# SCH_transistor-as-switch_2025-12-18.net
KiCad netlist of a schematic drawn in EasyEDA
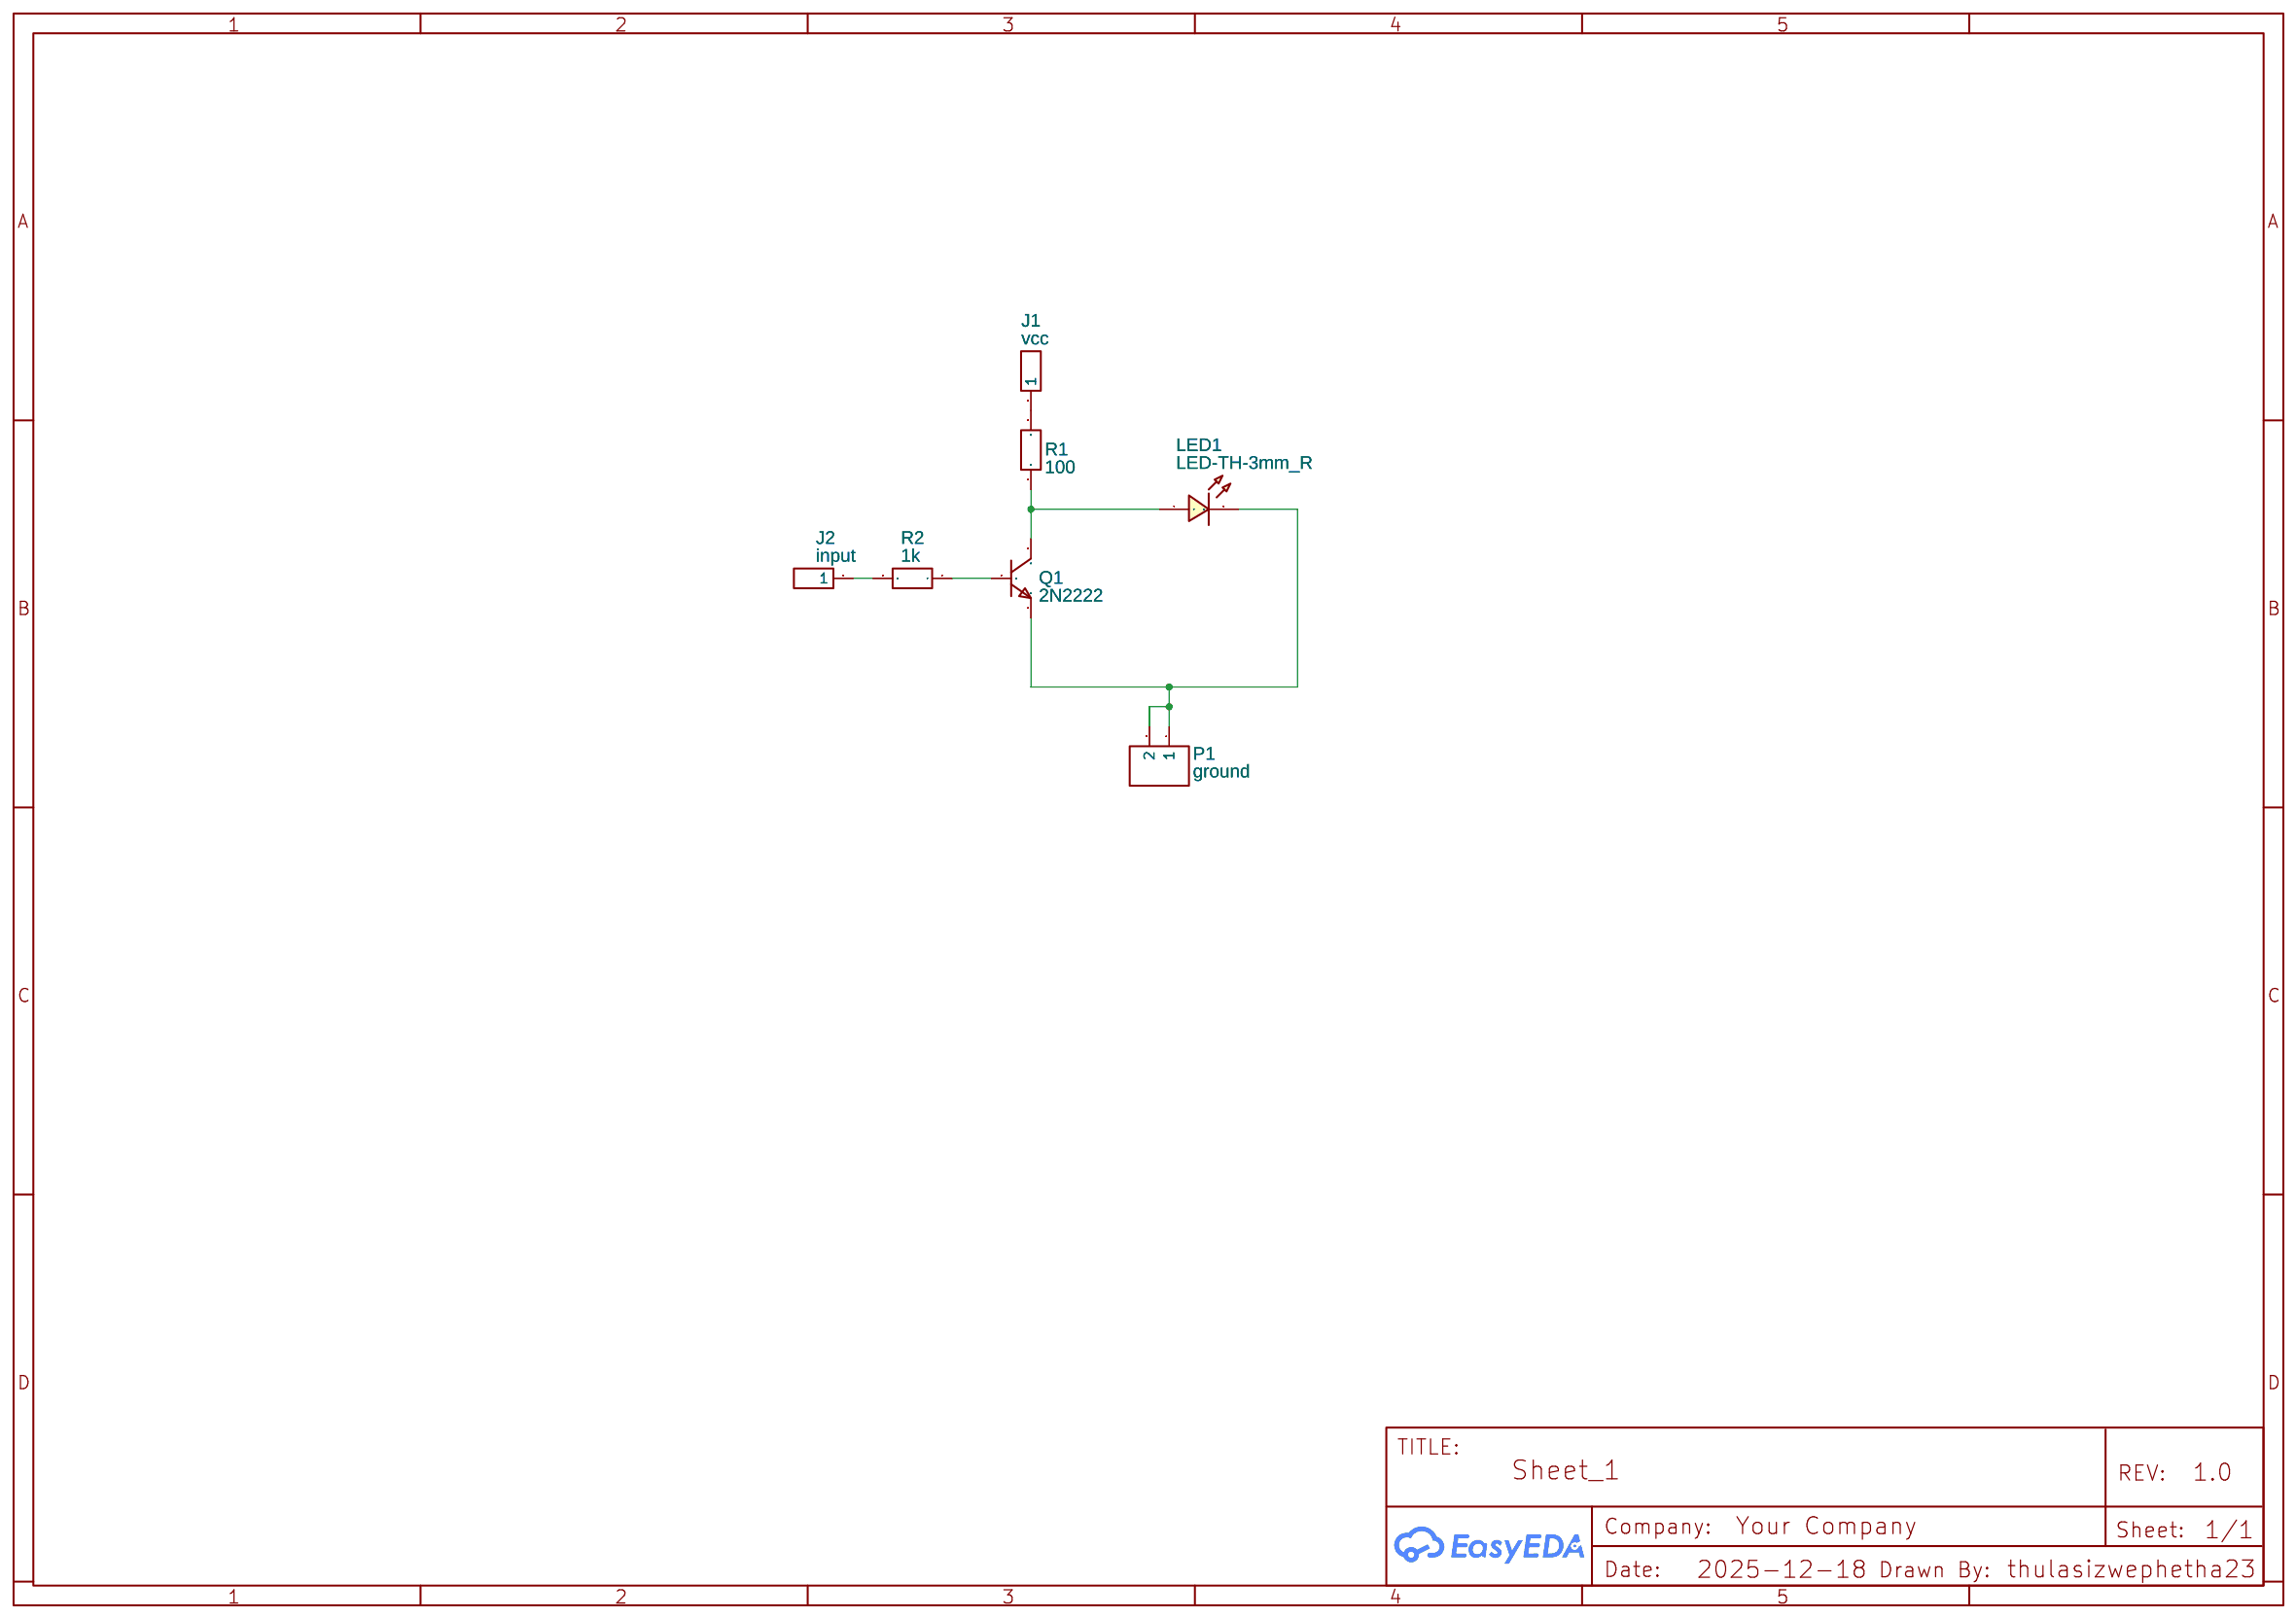
[diagram p0: schematic sheet]

(export (version "E")
  (design (tool "Eeschema 10.0.6"))
  (components
    (comp (ref "J1") (value "vcc") (libsource (lib "") (part "HDR-M-2.54_1x1_1")))
    (comp (ref "J2") (value "input") (libsource (lib "") (part "HDR-M-2.54_1x1")))
    (comp (ref "LED1")
      (value "LED-TH-3mm_R")
      (fields
        (field (name "Manufacturer Part") "204-10SDRD/S530-A3-L")
        (field (name "Manufacturer") "EVERLIGHT(台湾亿光)")
      )
      (libsource (lib "") (part "LED-TH-3mm_R"))
    )
    (comp (ref "P1") (value "ground") (libsource (lib "") (part "CONN-TH_2P-P5.00")))
    (comp (ref "Q1")
      (value "2N2222")
      (fields (field (name "Manufacturer Part") "2N2222A") (field (name "Manufacturer") "ST(先科)"))
      (libsource (lib "") (part "2N2222"))
    )
    (comp (ref "R1") (value "100") (libsource (lib "") (part "R_AXIAL-0.3_EU")))
    (comp (ref "R2") (value "1k") (libsource (lib "") (part "R_AXIAL-0.3_EU_1")))
  )
  (nets
    (net (code "1") (name "Net-(J1-Pad1)") (class "Default")
      (node (ref "J1") (pin "1") (pinfunction "1_1") (pintype "input"))
      (node (ref "R1") (pin "2") (pinfunction "2_2") (pintype "unspecified"))
    )
    (net (code "2") (name "Net-(J2-Pad1)") (class "Default")
      (node (ref "J2") (pin "1") (pinfunction "1_1") (pintype "input"))
      (node (ref "R2") (pin "2") (pinfunction "2_2") (pintype "unspecified"))
    )
    (net (code "3") (name "Net-(Q1-B)") (class "Default")
      (node (ref "Q1") (pin "2") (pinfunction "B_2") (pintype "unspecified"))
      (node (ref "R2") (pin "1") (pinfunction "1_1") (pintype "unspecified"))
    )
    (net (code "4") (name "Net-(Q1-C)") (class "Default")
      (node (ref "LED1") (pin "1") (pinfunction "1_1") (pintype "unspecified"))
      (node (ref "Q1") (pin "3") (pinfunction "C_3") (pintype "unspecified"))
      (node (ref "R1") (pin "1") (pinfunction "1_1") (pintype "unspecified"))
    )
    (net (code "5") (name "Net-(Q1-E)") (class "Default")
      (node (ref "LED1") (pin "2") (pinfunction "2_2") (pintype "unspecified"))
      (node (ref "P1") (pin "1") (pinfunction "1_1") (pintype "unspecified"))
      (node (ref "P1") (pin "2") (pinfunction "2_2") (pintype "unspecified"))
      (node (ref "Q1") (pin "1") (pinfunction "E_1") (pintype "unspecified"))
    )
  )
)
